# ProProject_TDeck_18650_Charger_2024-02-1.net
KiCad netlist of a schematic drawn in EasyEDA Pro
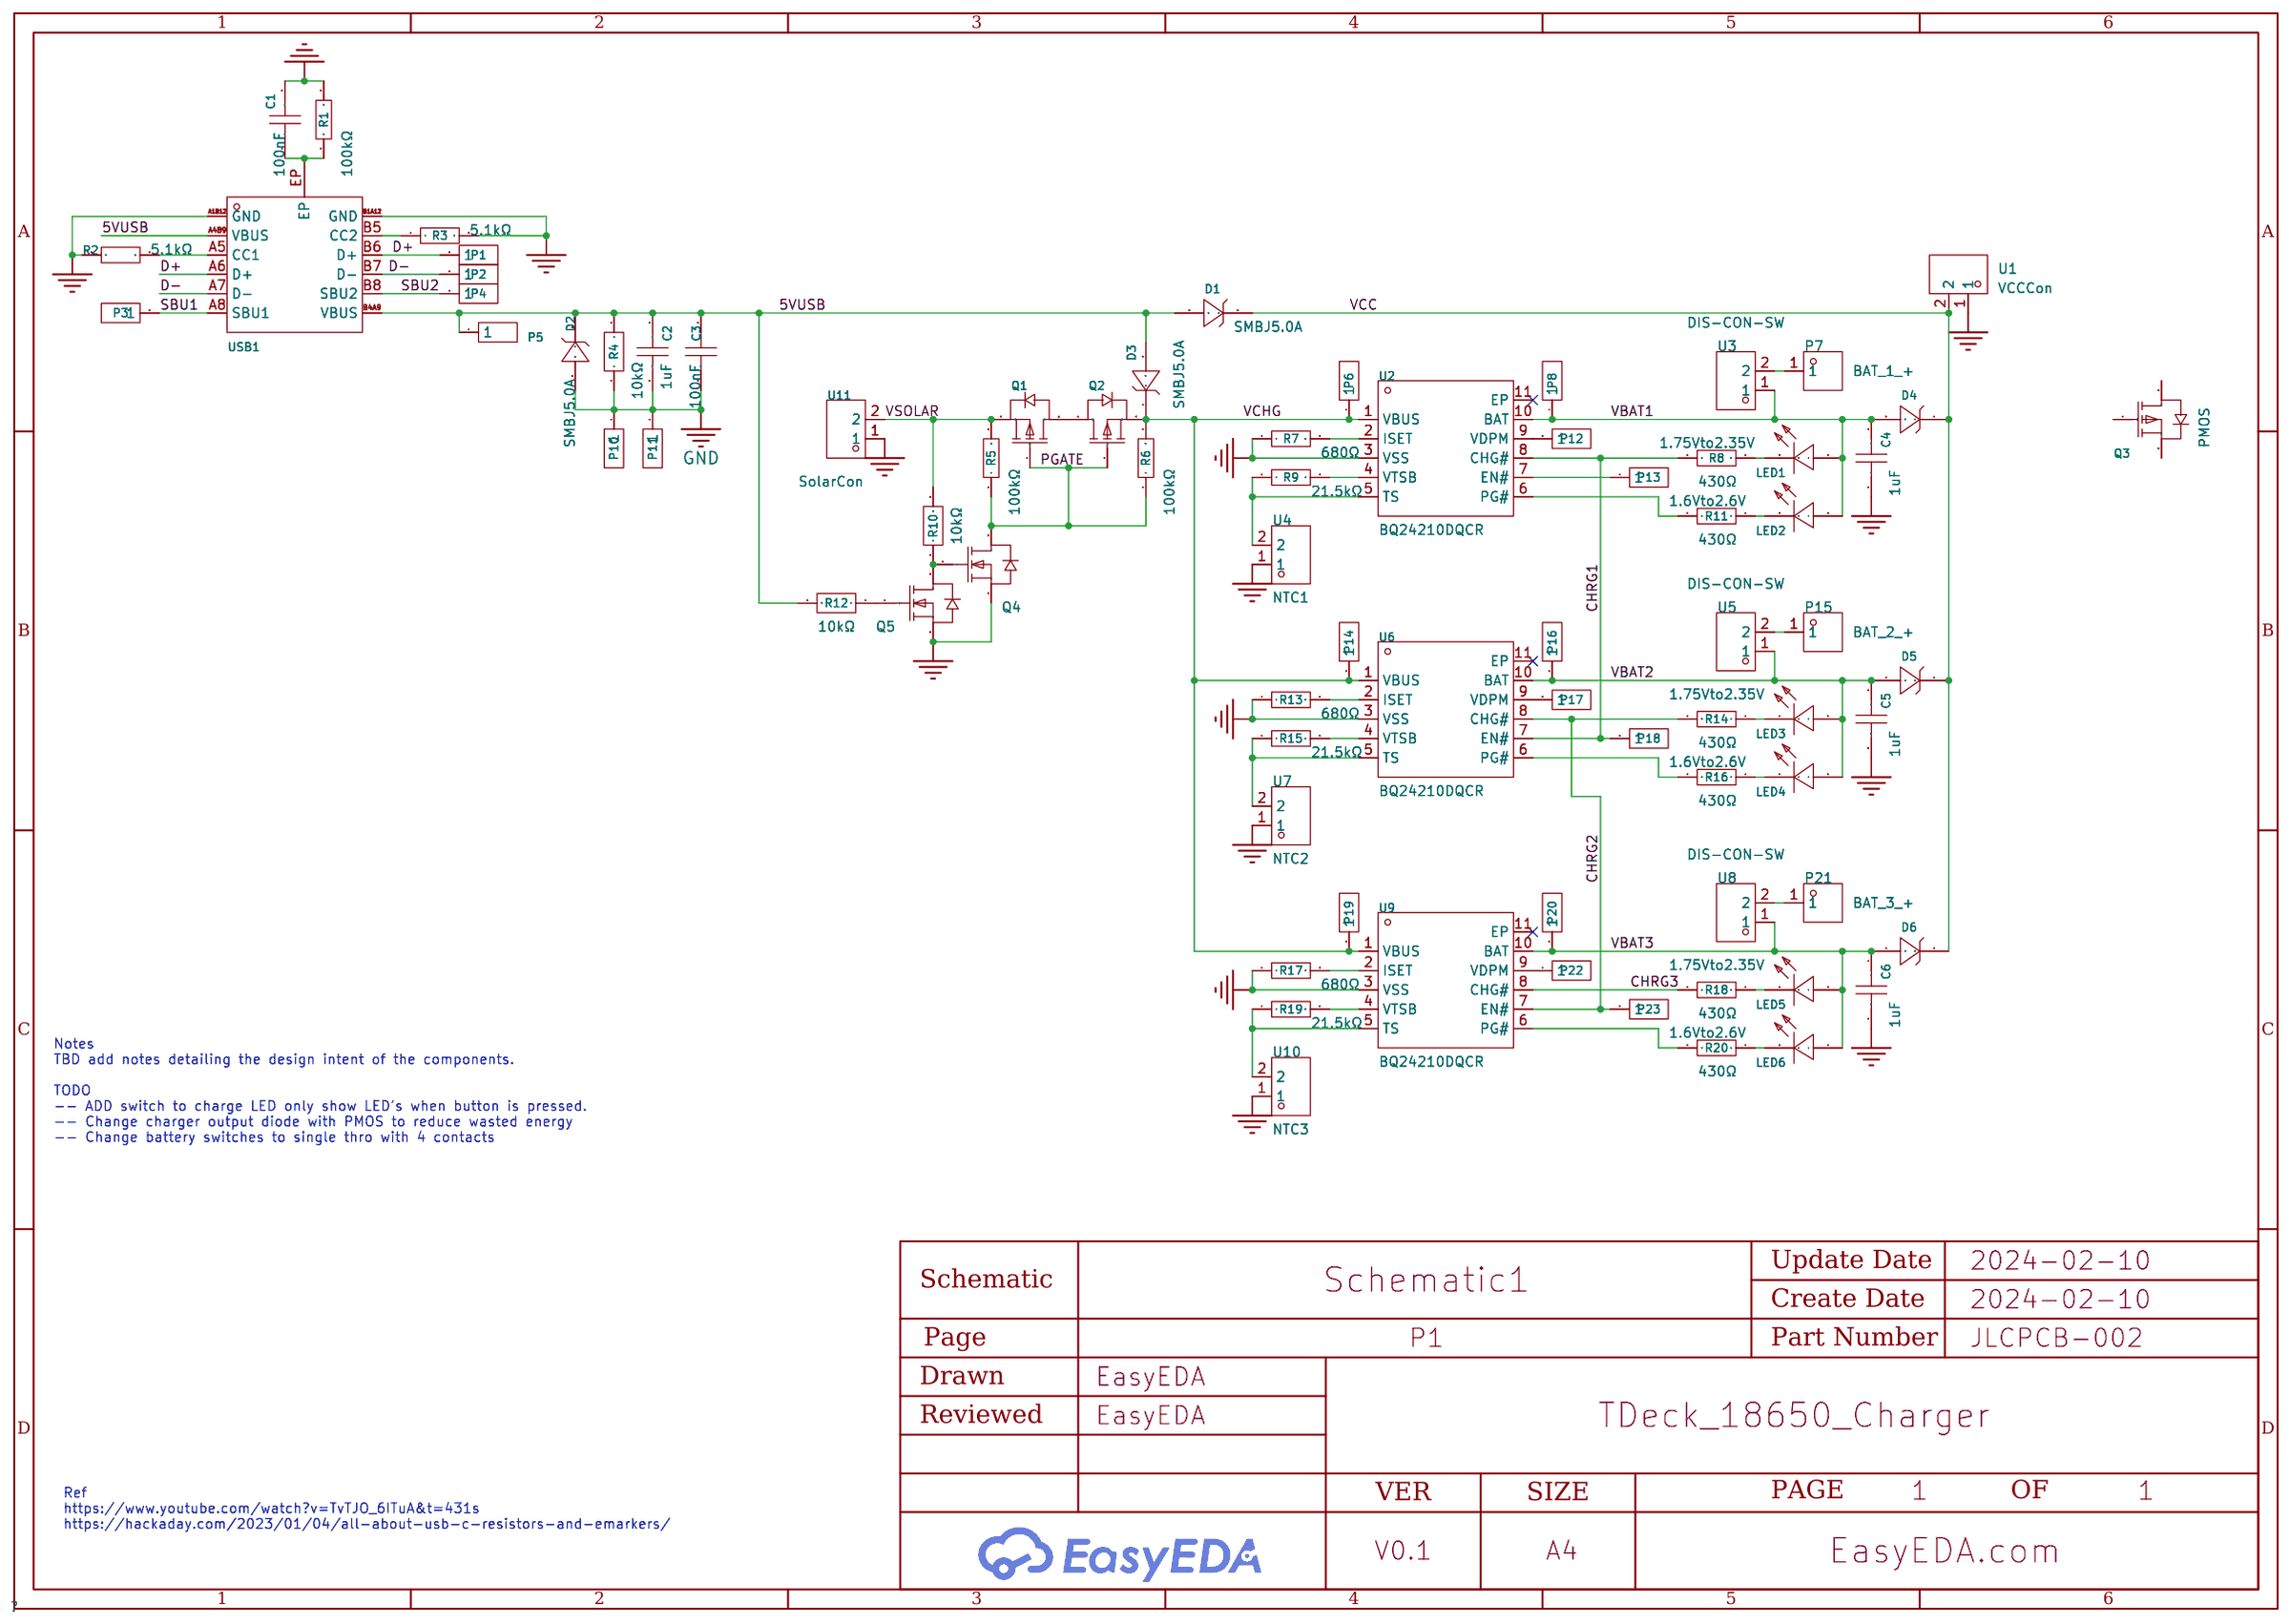
[diagram p0: schematic sheet]

(export (version "E")
  (design (tool "Eeschema 10.0.6"))
  (components
    (comp (ref "C1")
      (value "100nF")
      (footprint "easyedapro:C0603")
      (fields
        (field (name "Manufacturer Part") "CC0603KRX7R9BB104")
        (field (name "Manufacturer") "YAGEO(国巨)")
      )
      (libsource (lib "easyedapro") (part "CC0603KRX7R9BB104"))
    )
    (comp (ref "C2")
      (value "1uF")
      (footprint "easyedapro:C1206")
      (fields
        (field (name "Manufacturer Part") "CL31B105KCHNNNE")
        (field (name "Manufacturer") "SAMSUNG(三星)")
      )
      (libsource (lib "easyedapro") (part "CL31B105KCHNNNE"))
    )
    (comp (ref "C3")
      (value "100nF")
      (footprint "easyedapro:C0603")
      (fields
        (field (name "Manufacturer Part") "CC0603KRX7R9BB104")
        (field (name "Manufacturer") "YAGEO(国巨)")
      )
      (libsource (lib "easyedapro") (part "CC0603KRX7R9BB104"))
    )
    (comp (ref "C4")
      (value "1uF")
      (footprint "easyedapro:C1206")
      (fields
        (field (name "Manufacturer Part") "CL31B105KCHNNNE")
        (field (name "Manufacturer") "SAMSUNG(三星)")
      )
      (libsource (lib "easyedapro") (part "CL31B105KCHNNNE"))
    )
    (comp (ref "C5")
      (value "1uF")
      (footprint "easyedapro:C1206")
      (fields
        (field (name "Manufacturer Part") "CL31B105KCHNNNE")
        (field (name "Manufacturer") "SAMSUNG(三星)")
      )
      (libsource (lib "easyedapro") (part "CL31B105KCHNNNE"))
    )
    (comp (ref "C6")
      (value "1uF")
      (footprint "easyedapro:C1206")
      (fields
        (field (name "Manufacturer Part") "CL31B105KCHNNNE")
        (field (name "Manufacturer") "SAMSUNG(三星)")
      )
      (libsource (lib "easyedapro") (part "CL31B105KCHNNNE"))
    )
    (comp (ref "D1")
      (value "SMBJ5.0A")
      (footprint "easyedapro:SMB_L4.4-W3.6-LS5.2-RD")
      (fields (field (name "Manufacturer") "PAKER(派克微)"))
      (libsource (lib "easyedapro") (part "SMBJ5.0A_C3012487"))
    )
    (comp (ref "D2")
      (value "SMBJ5.0A")
      (footprint "easyedapro:SMB_L4.4-W3.6-LS5.2-RD")
      (fields (field (name "Manufacturer") "PAKER(派克微)"))
      (libsource (lib "easyedapro") (part "SMBJ5.0A_C3012487"))
    )
    (comp (ref "D3")
      (value "SMBJ5.0A")
      (footprint "easyedapro:SMB_L4.4-W3.6-LS5.2-RD")
      (fields (field (name "Manufacturer") "PAKER(派克微)"))
      (libsource (lib "easyedapro") (part "SMBJ5.0A_C3012487"))
    )
    (comp (ref "D4")
      (value "SMBJ5.0A")
      (footprint "easyedapro:SMB_L4.4-W3.6-LS5.2-RD")
      (fields (field (name "Manufacturer") "PAKER(派克微)"))
      (libsource (lib "easyedapro") (part "SMBJ5.0A_C3012487"))
    )
    (comp (ref "D5")
      (value "SMBJ5.0A")
      (footprint "easyedapro:SMB_L4.4-W3.6-LS5.2-RD")
      (fields (field (name "Manufacturer") "PAKER(派克微)"))
      (libsource (lib "easyedapro") (part "SMBJ5.0A_C3012487"))
    )
    (comp (ref "D6")
      (value "SMBJ5.0A")
      (footprint "easyedapro:SMB_L4.4-W3.6-LS5.2-RD")
      (fields (field (name "Manufacturer") "PAKER(派克微)"))
      (libsource (lib "easyedapro") (part "SMBJ5.0A_C3012487"))
    )
    (comp (ref "LED1")
      (value "1.75Vto2.35V")
      (footprint "easyedapro:LED0805-RD")
      (description "Emitted Color:Red")
      (fields
        (field (name "Manufacturer Part") "17-21/R6C-AQ2R2B/3T")
        (field (name "Manufacturer") "EVERLIGHT(亿光)")
      )
      (libsource (lib "easyedapro") (part "17-21/R6C-AQ2R2B/3T"))
    )
    (comp (ref "LED2")
      (value "1.6Vto2.6V")
      (footprint "easyedapro:LED0603-RD")
      (fields (field (name "Manufacturer Part") "NCD0603O2") (field (name "Manufacturer") "国星光电"))
      (libsource (lib "easyedapro") (part "FC-1608YOXK-600H08"))
    )
    (comp (ref "LED3")
      (value "1.75Vto2.35V")
      (footprint "easyedapro:LED0805-RD")
      (description "Emitted Color:Red")
      (fields
        (field (name "Manufacturer Part") "17-21/R6C-AQ2R2B/3T")
        (field (name "Manufacturer") "EVERLIGHT(亿光)")
      )
      (libsource (lib "easyedapro") (part "17-21/R6C-AQ2R2B/3T"))
    )
    (comp (ref "LED4")
      (value "1.6Vto2.6V")
      (footprint "easyedapro:LED0603-RD")
      (fields (field (name "Manufacturer Part") "NCD0603O2") (field (name "Manufacturer") "国星光电"))
      (libsource (lib "easyedapro") (part "FC-1608YOXK-600H08"))
    )
    (comp (ref "LED5")
      (value "1.75Vto2.35V")
      (footprint "easyedapro:LED0805-RD")
      (description "Emitted Color:Red")
      (fields
        (field (name "Manufacturer Part") "17-21/R6C-AQ2R2B/3T")
        (field (name "Manufacturer") "EVERLIGHT(亿光)")
      )
      (libsource (lib "easyedapro") (part "17-21/R6C-AQ2R2B/3T"))
    )
    (comp (ref "LED6")
      (value "1.6Vto2.6V")
      (footprint "easyedapro:LED0603-RD")
      (fields (field (name "Manufacturer Part") "NCD0603O2") (field (name "Manufacturer") "国星光电"))
      (libsource (lib "easyedapro") (part "FC-1608YOXK-600H08"))
    )
    (comp (ref "P1")
      (value "2.54-1*1P针")
      (footprint "easyedapro:HDR-TH_1P-P2.54-V-M")
      (fields (field (name "Manufacturer") "BOOMELE(博穆精密)"))
      (libsource (lib "easyedapro") (part "Header-Male-2.54_1x1"))
    )
    (comp (ref "P2")
      (value "2.54-1*1P针")
      (footprint "easyedapro:HDR-TH_1P-P2.54-V-M")
      (fields (field (name "Manufacturer") "BOOMELE(博穆精密)"))
      (libsource (lib "easyedapro") (part "Header-Male-2.54_1x1"))
    )
    (comp (ref "P3")
      (value "2.54-1*1P针")
      (footprint "easyedapro:HDR-TH_1P-P2.54-V-M")
      (fields (field (name "Manufacturer") "BOOMELE(博穆精密)"))
      (libsource (lib "easyedapro") (part "Header-Male-2.54_1x1"))
    )
    (comp (ref "P4")
      (value "2.54-1*1P针")
      (footprint "easyedapro:HDR-TH_1P-P2.54-V-M")
      (fields (field (name "Manufacturer") "BOOMELE(博穆精密)"))
      (libsource (lib "easyedapro") (part "Header-Male-2.54_1x1"))
    )
    (comp (ref "P5")
      (value "2.54-1*1P针")
      (footprint "easyedapro:HDR-TH_1P-P2.54-V-M")
      (fields (field (name "Manufacturer") "BOOMELE(博穆精密)"))
      (libsource (lib "easyedapro") (part "Header-Male-2.54_1x1"))
    )
    (comp (ref "P6")
      (value "2.54-1*1P针")
      (footprint "easyedapro:HDR-TH_1P-P2.54-V-M")
      (fields (field (name "Manufacturer") "BOOMELE(博穆精密)"))
      (libsource (lib "easyedapro") (part "Header-Male-2.54_1x1"))
    )
    (comp (ref "P7")
      (value "BAT_1_+")
      (footprint "easyedapro:SMD_BD4.0-L4.0-W4.0-D1.0")
      (fields (field (name "Manufacturer Part") "PAD"))
      (libsource (lib "easyedapro") (part "PAD"))
    )
    (comp (ref "P8")
      (value "2.54-1*1P针")
      (footprint "easyedapro:HDR-TH_1P-P2.54-V-M")
      (fields (field (name "Manufacturer") "BOOMELE(博穆精密)"))
      (libsource (lib "easyedapro") (part "Header-Male-2.54_1x1"))
    )
    (comp (ref "P10")
      (value "2.54-1*1P针")
      (footprint "easyedapro:HDR-TH_1P-P2.54-V-M")
      (fields (field (name "Manufacturer") "BOOMELE(博穆精密)"))
      (libsource (lib "easyedapro") (part "Header-Male-2.54_1x1"))
    )
    (comp (ref "P11")
      (value "2.54-1*1P针")
      (footprint "easyedapro:HDR-TH_1P-P2.54-V-M")
      (fields (field (name "Manufacturer") "BOOMELE(博穆精密)"))
      (libsource (lib "easyedapro") (part "Header-Male-2.54_1x1"))
    )
    (comp (ref "P12")
      (value "2.54-1*1P针")
      (footprint "easyedapro:HDR-TH_1P-P2.54-V-M")
      (fields (field (name "Manufacturer") "BOOMELE(博穆精密)"))
      (libsource (lib "easyedapro") (part "Header-Male-2.54_1x1"))
    )
    (comp (ref "P13")
      (value "2.54-1*1P针")
      (footprint "easyedapro:HDR-TH_1P-P2.54-V-M")
      (fields (field (name "Manufacturer") "BOOMELE(博穆精密)"))
      (libsource (lib "easyedapro") (part "Header-Male-2.54_1x1"))
    )
    (comp (ref "P14")
      (value "2.54-1*1P针")
      (footprint "easyedapro:HDR-TH_1P-P2.54-V-M")
      (fields (field (name "Manufacturer") "BOOMELE(博穆精密)"))
      (libsource (lib "easyedapro") (part "Header-Male-2.54_1x1"))
    )
    (comp (ref "P15")
      (value "BAT_2_+")
      (footprint "easyedapro:SMD_BD4.0-L4.0-W4.0-D1.0")
      (fields (field (name "Manufacturer Part") "PAD"))
      (libsource (lib "easyedapro") (part "PAD"))
    )
    (comp (ref "P16")
      (value "2.54-1*1P针")
      (footprint "easyedapro:HDR-TH_1P-P2.54-V-M")
      (fields (field (name "Manufacturer") "BOOMELE(博穆精密)"))
      (libsource (lib "easyedapro") (part "Header-Male-2.54_1x1"))
    )
    (comp (ref "P17")
      (value "2.54-1*1P针")
      (footprint "easyedapro:HDR-TH_1P-P2.54-V-M")
      (fields (field (name "Manufacturer") "BOOMELE(博穆精密)"))
      (libsource (lib "easyedapro") (part "Header-Male-2.54_1x1"))
    )
    (comp (ref "P18")
      (value "2.54-1*1P针")
      (footprint "easyedapro:HDR-TH_1P-P2.54-V-M")
      (fields (field (name "Manufacturer") "BOOMELE(博穆精密)"))
      (libsource (lib "easyedapro") (part "Header-Male-2.54_1x1"))
    )
    (comp (ref "P19")
      (value "2.54-1*1P针")
      (footprint "easyedapro:HDR-TH_1P-P2.54-V-M")
      (fields (field (name "Manufacturer") "BOOMELE(博穆精密)"))
      (libsource (lib "easyedapro") (part "Header-Male-2.54_1x1"))
    )
    (comp (ref "P20")
      (value "2.54-1*1P针")
      (footprint "easyedapro:HDR-TH_1P-P2.54-V-M")
      (fields (field (name "Manufacturer") "BOOMELE(博穆精密)"))
      (libsource (lib "easyedapro") (part "Header-Male-2.54_1x1"))
    )
    (comp (ref "P21")
      (value "BAT_3_+")
      (footprint "easyedapro:SMD_BD4.0-L4.0-W4.0-D1.0")
      (fields (field (name "Manufacturer Part") "PAD"))
      (libsource (lib "easyedapro") (part "PAD"))
    )
    (comp (ref "P22")
      (value "2.54-1*1P针")
      (footprint "easyedapro:HDR-TH_1P-P2.54-V-M")
      (fields (field (name "Manufacturer") "BOOMELE(博穆精密)"))
      (libsource (lib "easyedapro") (part "Header-Male-2.54_1x1"))
    )
    (comp (ref "P23")
      (value "2.54-1*1P针")
      (footprint "easyedapro:HDR-TH_1P-P2.54-V-M")
      (fields (field (name "Manufacturer") "BOOMELE(博穆精密)"))
      (libsource (lib "easyedapro") (part "Header-Male-2.54_1x1"))
    )
    (comp (ref "Q1")
      (value "SI2301")
      (footprint "easyedapro:SOT-23-3_L2.9-W1.3-P1.90-LS2.4-BR")
      (fields (field (name "Manufacturer") "YONGYUTAI(永裕泰)"))
      (libsource (lib "easyedapro") (part "SI2301_C2891731"))
    )
    (comp (ref "Q2")
      (value "SI2301")
      (footprint "easyedapro:SOT-23-3_L2.9-W1.3-P1.90-LS2.4-BR")
      (fields (field (name "Manufacturer") "YONGYUTAI(永裕泰)"))
      (libsource (lib "easyedapro") (part "SI2301_C2891731"))
    )
    (comp (ref "Q3")
      (value "PMOS")
      (footprint "easyedapro:SOT-23-3_L2.9-W1.3-P1.90-LS2.4-BR")
      (fields (field (name "Manufacturer Part") "SI2301") (field (name "Manufacturer") "YONGYUTAI(永裕泰)"))
      (libsource (lib "easyedapro") (part "SI2301_C2891731"))
    )
    (comp (ref "Q4")
      (value "AO3400A")
      (footprint "easyedapro:SOT-23-3_L2.9-W1.6-P1.90-LS2.8-BR")
      (fields (field (name "Manufacturer") "AOS"))
      (libsource (lib "easyedapro") (part "AO3400A"))
    )
    (comp (ref "Q5")
      (value "AO3400A")
      (footprint "easyedapro:SOT-23-3_L2.9-W1.6-P1.90-LS2.8-BR")
      (fields (field (name "Manufacturer") "AOS"))
      (libsource (lib "easyedapro") (part "AO3400A"))
    )
    (comp (ref "R1")
      (value "100kΩ")
      (footprint "easyedapro:R0805")
      (fields
        (field (name "Manufacturer Part") "0805W8F1003T5E")
        (field (name "Manufacturer") "UNI-ROYAL(厚声)")
      )
      (libsource (lib "easyedapro") (part "0805W8F1003T5E_C149504"))
    )
    (comp (ref "R2")
      (value "5.1kΩ")
      (footprint "easyedapro:R0805")
      (fields
        (field (name "Manufacturer Part") "0805W8F5101T5E")
        (field (name "Manufacturer") "UNI-ROYAL(厚声)")
      )
      (libsource (lib "easyedapro") (part "0805W8F5101T5E"))
    )
    (comp (ref "R3")
      (value "5.1kΩ")
      (footprint "easyedapro:R0805")
      (fields
        (field (name "Manufacturer Part") "0805W8F5101T5E")
        (field (name "Manufacturer") "UNI-ROYAL(厚声)")
      )
      (libsource (lib "easyedapro") (part "0805W8F5101T5E"))
    )
    (comp (ref "R4")
      (value "10kΩ")
      (footprint "easyedapro:R0805")
      (fields (field (name "Manufacturer Part") "AR05DTD1002") (field (name "Manufacturer") "Viking(光颉)"))
      (libsource (lib "easyedapro") (part "AR05DTD1002"))
    )
    (comp (ref "R5")
      (value "100kΩ")
      (footprint "easyedapro:R0805")
      (fields
        (field (name "Manufacturer Part") "0805W8F1003T5E")
        (field (name "Manufacturer") "UNI-ROYAL(厚声)")
      )
      (libsource (lib "easyedapro") (part "0805W8F1003T5E_C149504"))
    )
    (comp (ref "R6")
      (value "100kΩ")
      (footprint "easyedapro:R0805")
      (fields
        (field (name "Manufacturer Part") "0805W8F1003T5E")
        (field (name "Manufacturer") "UNI-ROYAL(厚声)")
      )
      (libsource (lib "easyedapro") (part "0805W8F1003T5E_C149504"))
    )
    (comp (ref "R7")
      (value "680Ω")
      (footprint "easyedapro:R0805")
      (fields
        (field (name "Manufacturer Part") "0805W8F6800T5E")
        (field (name "Manufacturer") "UNI-ROYAL(厚声)")
      )
      (libsource (lib "easyedapro") (part "0805W8F6800T5E"))
    )
    (comp (ref "R8")
      (value "430Ω")
      (footprint "easyedapro:R0603")
      (fields
        (field (name "Manufacturer Part") "0603WAF4300T5E")
        (field (name "Manufacturer") "UNI-ROYAL(厚声)")
      )
      (libsource (lib "easyedapro") (part "0603WAF4300T5E"))
    )
    (comp (ref "R9")
      (value "21.5kΩ")
      (footprint "easyedapro:R0805")
      (fields (field (name "Manufacturer Part") "CR0805-FX-2152ELF") (field (name "Manufacturer") "BOURNS"))
      (libsource (lib "easyedapro") (part "CR0805-FX-2152ELF"))
    )
    (comp (ref "R10")
      (value "10kΩ")
      (footprint "easyedapro:R0805")
      (fields (field (name "Manufacturer Part") "AR05DTD1002") (field (name "Manufacturer") "Viking(光颉)"))
      (libsource (lib "easyedapro") (part "AR05DTD1002"))
    )
    (comp (ref "R11")
      (value "430Ω")
      (footprint "easyedapro:R0603")
      (fields
        (field (name "Manufacturer Part") "0603WAF4300T5E")
        (field (name "Manufacturer") "UNI-ROYAL(厚声)")
      )
      (libsource (lib "easyedapro") (part "0603WAF4300T5E"))
    )
    (comp (ref "R12")
      (value "10kΩ")
      (footprint "easyedapro:R0805")
      (fields (field (name "Manufacturer Part") "AR05DTD1002") (field (name "Manufacturer") "Viking(光颉)"))
      (libsource (lib "easyedapro") (part "AR05DTD1002"))
    )
    (comp (ref "R13")
      (value "680Ω")
      (footprint "easyedapro:R0805")
      (fields
        (field (name "Manufacturer Part") "0805W8F6800T5E")
        (field (name "Manufacturer") "UNI-ROYAL(厚声)")
      )
      (libsource (lib "easyedapro") (part "0805W8F6800T5E"))
    )
    (comp (ref "R14")
      (value "430Ω")
      (footprint "easyedapro:R0603")
      (fields
        (field (name "Manufacturer Part") "0603WAF4300T5E")
        (field (name "Manufacturer") "UNI-ROYAL(厚声)")
      )
      (libsource (lib "easyedapro") (part "0603WAF4300T5E"))
    )
    (comp (ref "R15")
      (value "21.5kΩ")
      (footprint "easyedapro:R0805")
      (fields (field (name "Manufacturer Part") "CR0805-FX-2152ELF") (field (name "Manufacturer") "BOURNS"))
      (libsource (lib "easyedapro") (part "CR0805-FX-2152ELF"))
    )
    (comp (ref "R16")
      (value "430Ω")
      (footprint "easyedapro:R0603")
      (fields
        (field (name "Manufacturer Part") "0603WAF4300T5E")
        (field (name "Manufacturer") "UNI-ROYAL(厚声)")
      )
      (libsource (lib "easyedapro") (part "0603WAF4300T5E"))
    )
    (comp (ref "R17")
      (value "680Ω")
      (footprint "easyedapro:R0805")
      (fields
        (field (name "Manufacturer Part") "0805W8F6800T5E")
        (field (name "Manufacturer") "UNI-ROYAL(厚声)")
      )
      (libsource (lib "easyedapro") (part "0805W8F6800T5E"))
    )
    (comp (ref "R18")
      (value "430Ω")
      (footprint "easyedapro:R0603")
      (fields
        (field (name "Manufacturer Part") "0603WAF4300T5E")
        (field (name "Manufacturer") "UNI-ROYAL(厚声)")
      )
      (libsource (lib "easyedapro") (part "0603WAF4300T5E"))
    )
    (comp (ref "R19")
      (value "21.5kΩ")
      (footprint "easyedapro:R0805")
      (fields (field (name "Manufacturer Part") "CR0805-FX-2152ELF") (field (name "Manufacturer") "BOURNS"))
      (libsource (lib "easyedapro") (part "CR0805-FX-2152ELF"))
    )
    (comp (ref "R20")
      (value "430Ω")
      (footprint "easyedapro:R0603")
      (fields
        (field (name "Manufacturer Part") "0603WAF4300T5E")
        (field (name "Manufacturer") "UNI-ROYAL(厚声)")
      )
      (libsource (lib "easyedapro") (part "0603WAF4300T5E"))
    )
    (comp (ref "U1")
      (value "VCCCon")
      (footprint "easyedapro:HDR-TH_2P-P2.54-V-M-2")
      (fields
        (field (name "Manufacturer Part") "5-146472-2")
        (field (name "Manufacturer") "TE Connectivity(泰科电子)")
      )
      (libsource (lib "easyedapro") (part "5-146472-2"))
    )
    (comp (ref "U2")
      (value "BQ24210DQCR")
      (footprint "easyedapro:WSON-10_L3.0-W2.0-P0.50-BL-EP")
      (fields (field (name "Manufacturer") "TI(德州仪器)"))
      (libsource (lib "easyedapro") (part "BQ24210DQCR"))
    )
    (comp (ref "U3")
      (value "DIS-CON-SW")
      (footprint "easyedapro:HDR-TH_2P-P2.54-V-M-2")
      (fields
        (field (name "Manufacturer Part") "5-146472-2")
        (field (name "Manufacturer") "TE Connectivity(泰科电子)")
      )
      (libsource (lib "easyedapro") (part "5-146472-2"))
    )
    (comp (ref "U4")
      (value "NTC1")
      (footprint "easyedapro:HDR-TH_2P-P2.54-V-M-2")
      (fields
        (field (name "Manufacturer Part") "5-146472-2")
        (field (name "Manufacturer") "TE Connectivity(泰科电子)")
      )
      (libsource (lib "easyedapro") (part "5-146472-2"))
    )
    (comp (ref "U5")
      (value "DIS-CON-SW")
      (footprint "easyedapro:HDR-TH_2P-P2.54-V-M-2")
      (fields
        (field (name "Manufacturer Part") "5-146472-2")
        (field (name "Manufacturer") "TE Connectivity(泰科电子)")
      )
      (libsource (lib "easyedapro") (part "5-146472-2"))
    )
    (comp (ref "U6")
      (value "BQ24210DQCR")
      (footprint "easyedapro:WSON-10_L3.0-W2.0-P0.50-BL-EP")
      (fields (field (name "Manufacturer") "TI(德州仪器)"))
      (libsource (lib "easyedapro") (part "BQ24210DQCR"))
    )
    (comp (ref "U7")
      (value "NTC2")
      (footprint "easyedapro:HDR-TH_2P-P2.54-V-M-2")
      (fields
        (field (name "Manufacturer Part") "5-146472-2")
        (field (name "Manufacturer") "TE Connectivity(泰科电子)")
      )
      (libsource (lib "easyedapro") (part "5-146472-2"))
    )
    (comp (ref "U8")
      (value "DIS-CON-SW")
      (footprint "easyedapro:HDR-TH_2P-P2.54-V-M-2")
      (fields
        (field (name "Manufacturer Part") "5-146472-2")
        (field (name "Manufacturer") "TE Connectivity(泰科电子)")
      )
      (libsource (lib "easyedapro") (part "5-146472-2"))
    )
    (comp (ref "U9")
      (value "BQ24210DQCR")
      (footprint "easyedapro:WSON-10_L3.0-W2.0-P0.50-BL-EP")
      (fields (field (name "Manufacturer") "TI(德州仪器)"))
      (libsource (lib "easyedapro") (part "BQ24210DQCR"))
    )
    (comp (ref "U10")
      (value "NTC3")
      (footprint "easyedapro:HDR-TH_2P-P2.54-V-M-2")
      (fields
        (field (name "Manufacturer Part") "5-146472-2")
        (field (name "Manufacturer") "TE Connectivity(泰科电子)")
      )
      (libsource (lib "easyedapro") (part "5-146472-2"))
    )
    (comp (ref "U11")
      (value "SolarCon")
      (footprint "easyedapro:CONN-TH_XY308-2.54-2P")
      (fields
        (field (name "Manufacturer Part") "XY308-2.54-2P")
        (field (name "Manufacturer") "XINLAIYA(新莱亚)")
      )
      (libsource (lib "easyedapro") (part "XY308-2.54-2P"))
    )
    (comp (ref "USB1")
      (value "TYPEC-304-ACP16")
      (footprint "easyedapro:USB-C-SMD_TYPE-C-16P-1")
      (fields (field (name "Manufacturer") "XUNPU(讯普)"))
      (libsource (lib "easyedapro") (part "TYPEC-304-ACP16"))
    )
  )
  (nets
    (net (code "1") (name "/5VUSB") (class "Default")
      (node (ref "C2") (pin "1") (pinfunction "1_1") (pintype "input"))
      (node (ref "C3") (pin "2") (pinfunction "2_2") (pintype "input"))
      (node (ref "D1") (pin "2") (pinfunction "2_2") (pintype "input"))
      (node (ref "D2") (pin "1") (pinfunction "1_1") (pintype "input"))
      (node (ref "D3") (pin "2") (pinfunction "2_2") (pintype "input"))
      (node (ref "P5") (pin "1") (pinfunction "1_1") (pintype "input"))
      (node (ref "R12") (pin "2") (pinfunction "2_2") (pintype "input"))
      (node (ref "R4") (pin "2") (pinfunction "2_2") (pintype "input"))
      (node (ref "USB1") (pin "A4B9") (pinfunction "VBUS_A4B9") (pintype "input"))
      (node (ref "USB1") (pin "B4A9") (pinfunction "VBUS_B4A9") (pintype "input"))
    )
    (net (code "2") (name "/CHRG1") (class "Default")
      (node (ref "P18") (pin "1") (pinfunction "1_1") (pintype "input"))
      (node (ref "R8") (pin "2") (pinfunction "2_2") (pintype "input"))
      (node (ref "U2") (pin "8") (pinfunction "CHG#_8") (pintype "input"))
      (node (ref "U6") (pin "7") (pinfunction "EN#_7") (pintype "input"))
    )
    (net (code "3") (name "/CHRG2") (class "Default")
      (node (ref "P23") (pin "1") (pinfunction "1_1") (pintype "input"))
      (node (ref "R14") (pin "2") (pinfunction "2_2") (pintype "input"))
      (node (ref "U6") (pin "8") (pinfunction "CHG#_8") (pintype "input"))
      (node (ref "U9") (pin "7") (pinfunction "EN#_7") (pintype "input"))
    )
    (net (code "4") (name "/CHRG3") (class "Default")
      (node (ref "R18") (pin "2") (pinfunction "2_2") (pintype "input"))
      (node (ref "U9") (pin "8") (pinfunction "CHG#_8") (pintype "input"))
    )
    (net (code "5") (name "/D+") (class "Default")
      (node (ref "P1") (pin "1") (pinfunction "1_1") (pintype "input"))
      (node (ref "USB1") (pin "A6") (pinfunction "D+_A6") (pintype "input"))
      (node (ref "USB1") (pin "B6") (pinfunction "D+_B6") (pintype "input"))
    )
    (net (code "6") (name "/D-") (class "Default")
      (node (ref "P2") (pin "1") (pinfunction "1_1") (pintype "input"))
      (node (ref "USB1") (pin "A7") (pinfunction "D-_A7") (pintype "input"))
      (node (ref "USB1") (pin "B7") (pinfunction "D-_B7") (pintype "input"))
    )
    (net (code "7") (name "/PGATE") (class "Default")
      (node (ref "Q1") (pin "1") (pinfunction "G_1") (pintype "input"))
      (node (ref "Q2") (pin "1") (pinfunction "G_1") (pintype "input"))
      (node (ref "Q4") (pin "3") (pinfunction "D_3") (pintype "input"))
      (node (ref "R5") (pin "1") (pinfunction "1_1") (pintype "input"))
      (node (ref "R6") (pin "1") (pinfunction "1_1") (pintype "input"))
    )
    (net (code "8") (name "/SBU1") (class "Default")
      (node (ref "P3") (pin "1") (pinfunction "1_1") (pintype "input"))
      (node (ref "USB1") (pin "A8") (pinfunction "SBU1_A8") (pintype "input"))
    )
    (net (code "9") (name "/SBU2") (class "Default")
      (node (ref "P4") (pin "1") (pinfunction "1_1") (pintype "input"))
      (node (ref "USB1") (pin "B8") (pinfunction "SBU2_B8") (pintype "input"))
    )
    (net (code "10") (name "/VBAT1") (class "Default")
      (node (ref "C4") (pin "1") (pinfunction "1_1") (pintype "input"))
      (node (ref "D4") (pin "2") (pinfunction "2_2") (pintype "input"))
      (node (ref "LED1") (pin "2") (pinfunction "A_2") (pintype "input"))
      (node (ref "LED2") (pin "2") (pinfunction "A_2") (pintype "input"))
      (node (ref "P8") (pin "1") (pinfunction "1_1") (pintype "input"))
      (node (ref "U2") (pin "10") (pinfunction "BAT_10") (pintype "input"))
      (node (ref "U3") (pin "1") (pinfunction "1_1") (pintype "unspecified"))
    )
    (net (code "11") (name "/VBAT2") (class "Default")
      (node (ref "C5") (pin "1") (pinfunction "1_1") (pintype "input"))
      (node (ref "D5") (pin "2") (pinfunction "2_2") (pintype "input"))
      (node (ref "LED3") (pin "2") (pinfunction "A_2") (pintype "input"))
      (node (ref "LED4") (pin "2") (pinfunction "A_2") (pintype "input"))
      (node (ref "P16") (pin "1") (pinfunction "1_1") (pintype "input"))
      (node (ref "U5") (pin "1") (pinfunction "1_1") (pintype "unspecified"))
      (node (ref "U6") (pin "10") (pinfunction "BAT_10") (pintype "input"))
    )
    (net (code "12") (name "/VBAT3") (class "Default")
      (node (ref "C6") (pin "1") (pinfunction "1_1") (pintype "input"))
      (node (ref "D6") (pin "2") (pinfunction "2_2") (pintype "input"))
      (node (ref "LED5") (pin "2") (pinfunction "A_2") (pintype "input"))
      (node (ref "LED6") (pin "2") (pinfunction "A_2") (pintype "input"))
      (node (ref "P20") (pin "1") (pinfunction "1_1") (pintype "input"))
      (node (ref "U8") (pin "1") (pinfunction "1_1") (pintype "unspecified"))
      (node (ref "U9") (pin "10") (pinfunction "BAT_10") (pintype "input"))
    )
    (net (code "13") (name "/VCC") (class "Default")
      (node (ref "D1") (pin "1") (pinfunction "1_1") (pintype "input"))
      (node (ref "D4") (pin "1") (pinfunction "1_1") (pintype "input"))
      (node (ref "D5") (pin "1") (pinfunction "1_1") (pintype "input"))
      (node (ref "D6") (pin "1") (pinfunction "1_1") (pintype "input"))
      (node (ref "U1") (pin "2") (pinfunction "2_2") (pintype "unspecified"))
    )
    (net (code "14") (name "/VCHG") (class "Default")
      (node (ref "D3") (pin "1") (pinfunction "1_1") (pintype "input"))
      (node (ref "P14") (pin "1") (pinfunction "1_1") (pintype "input"))
      (node (ref "P19") (pin "1") (pinfunction "1_1") (pintype "input"))
      (node (ref "P6") (pin "1") (pinfunction "1_1") (pintype "input"))
      (node (ref "Q2") (pin "2") (pinfunction "S_2") (pintype "input"))
      (node (ref "R6") (pin "2") (pinfunction "2_2") (pintype "input"))
      (node (ref "U2") (pin "1") (pinfunction "VBUS_1") (pintype "input"))
      (node (ref "U6") (pin "1") (pinfunction "VBUS_1") (pintype "input"))
      (node (ref "U9") (pin "1") (pinfunction "VBUS_1") (pintype "input"))
    )
    (net (code "15") (name "/VSOLAR") (class "Default")
      (node (ref "Q1") (pin "2") (pinfunction "S_2") (pintype "input"))
      (node (ref "R10") (pin "2") (pinfunction "2_2") (pintype "input"))
      (node (ref "R5") (pin "2") (pinfunction "2_2") (pintype "input"))
      (node (ref "U11") (pin "2") (pinfunction "2_2") (pintype "input"))
    )
    (net (code "16") (name "GND") (class "Default")
      (node (ref "C1") (pin "2") (pinfunction "2_2") (pintype "input"))
      (node (ref "C2") (pin "2") (pinfunction "2_2") (pintype "input"))
      (node (ref "C3") (pin "1") (pinfunction "1_1") (pintype "input"))
      (node (ref "C4") (pin "2") (pinfunction "2_2") (pintype "input"))
      (node (ref "C5") (pin "2") (pinfunction "2_2") (pintype "input"))
      (node (ref "C6") (pin "2") (pinfunction "2_2") (pintype "input"))
      (node (ref "D2") (pin "2") (pinfunction "2_2") (pintype "input"))
      (node (ref "P10") (pin "1") (pinfunction "1_1") (pintype "input"))
      (node (ref "P11") (pin "1") (pinfunction "1_1") (pintype "input"))
      (node (ref "Q4") (pin "2") (pinfunction "S_2") (pintype "input"))
      (node (ref "Q5") (pin "2") (pinfunction "S_2") (pintype "input"))
      (node (ref "R1") (pin "2") (pinfunction "2_2") (pintype "input"))
      (node (ref "R13") (pin "1") (pinfunction "1_1") (pintype "input"))
      (node (ref "R17") (pin "1") (pinfunction "1_1") (pintype "input"))
      (node (ref "R2") (pin "1") (pinfunction "1_1") (pintype "input"))
      (node (ref "R3") (pin "2") (pinfunction "2_2") (pintype "input"))
      (node (ref "R4") (pin "1") (pinfunction "1_1") (pintype "input"))
      (node (ref "R7") (pin "1") (pinfunction "1_1") (pintype "input"))
      (node (ref "U1") (pin "1") (pinfunction "1_1") (pintype "unspecified"))
      (node (ref "U10") (pin "1") (pinfunction "1_1") (pintype "unspecified"))
      (node (ref "U11") (pin "1") (pinfunction "1_1") (pintype "input"))
      (node (ref "U2") (pin "3") (pinfunction "VSS_3") (pintype "input"))
      (node (ref "U4") (pin "1") (pinfunction "1_1") (pintype "unspecified"))
      (node (ref "U6") (pin "3") (pinfunction "VSS_3") (pintype "input"))
      (node (ref "U7") (pin "1") (pinfunction "1_1") (pintype "unspecified"))
      (node (ref "U9") (pin "3") (pinfunction "VSS_3") (pintype "input"))
      (node (ref "USB1") (pin "A1B12") (pinfunction "GND_A1B12") (pintype "input"))
      (node (ref "USB1") (pin "B1A12") (pinfunction "GND_B1A12") (pintype "input"))
    )
    (net (code "17") (name "Net-(C1-Pad1)") (class "Default")
      (node (ref "C1") (pin "1") (pinfunction "1_1") (pintype "input"))
      (node (ref "R1") (pin "1") (pinfunction "1_1") (pintype "input"))
      (node (ref "USB1") (pin "EP") (pinfunction "EP_EP") (pintype "input"))
    )
    (net (code "18") (name "Net-(LED1-K)") (class "Default")
      (node (ref "LED1") (pin "1") (pinfunction "K_1") (pintype "input"))
      (node (ref "R8") (pin "1") (pinfunction "1_1") (pintype "input"))
    )
    (net (code "19") (name "Net-(LED2-K)") (class "Default")
      (node (ref "LED2") (pin "1") (pinfunction "K_1") (pintype "input"))
      (node (ref "R11") (pin "1") (pinfunction "1_1") (pintype "input"))
    )
    (net (code "20") (name "Net-(LED3-K)") (class "Default")
      (node (ref "LED3") (pin "1") (pinfunction "K_1") (pintype "input"))
      (node (ref "R14") (pin "1") (pinfunction "1_1") (pintype "input"))
    )
    (net (code "21") (name "Net-(LED4-K)") (class "Default")
      (node (ref "LED4") (pin "1") (pinfunction "K_1") (pintype "input"))
      (node (ref "R16") (pin "1") (pinfunction "1_1") (pintype "input"))
    )
    (net (code "22") (name "Net-(LED5-K)") (class "Default")
      (node (ref "LED5") (pin "1") (pinfunction "K_1") (pintype "input"))
      (node (ref "R18") (pin "1") (pinfunction "1_1") (pintype "input"))
    )
    (net (code "23") (name "Net-(LED6-K)") (class "Default")
      (node (ref "LED6") (pin "1") (pinfunction "K_1") (pintype "input"))
      (node (ref "R20") (pin "1") (pinfunction "1_1") (pintype "input"))
    )
    (net (code "24") (name "Net-(P7-Pad1)") (class "Default")
      (node (ref "P7") (pin "1") (pinfunction "1_1") (pintype "input"))
      (node (ref "U3") (pin "2") (pinfunction "2_2") (pintype "unspecified"))
    )
    (net (code "25") (name "Net-(P15-Pad1)") (class "Default")
      (node (ref "P15") (pin "1") (pinfunction "1_1") (pintype "input"))
      (node (ref "U5") (pin "2") (pinfunction "2_2") (pintype "unspecified"))
    )
    (net (code "26") (name "Net-(P21-Pad1)") (class "Default")
      (node (ref "P21") (pin "1") (pinfunction "1_1") (pintype "input"))
      (node (ref "U8") (pin "2") (pinfunction "2_2") (pintype "unspecified"))
    )
    (net (code "27") (name "Net-(Q1-D)") (class "Default")
      (node (ref "Q1") (pin "3") (pinfunction "D_3") (pintype "input"))
      (node (ref "Q2") (pin "3") (pinfunction "D_3") (pintype "input"))
    )
    (net (code "28") (name "Net-(Q4-G)") (class "Default")
      (node (ref "Q4") (pin "1") (pinfunction "G_1") (pintype "input"))
      (node (ref "Q5") (pin "3") (pinfunction "D_3") (pintype "input"))
      (node (ref "R10") (pin "1") (pinfunction "1_1") (pintype "input"))
    )
    (net (code "29") (name "Net-(Q5-G)") (class "Default")
      (node (ref "Q5") (pin "1") (pinfunction "G_1") (pintype "input"))
      (node (ref "R12") (pin "1") (pinfunction "1_1") (pintype "input"))
    )
    (net (code "30") (name "Net-(U2-EN#)") (class "Default")
      (node (ref "P13") (pin "1") (pinfunction "1_1") (pintype "input"))
      (node (ref "U2") (pin "7") (pinfunction "EN#_7") (pintype "input"))
    )
    (net (code "31") (name "Net-(U2-ISET)") (class "Default")
      (node (ref "R7") (pin "2") (pinfunction "2_2") (pintype "input"))
      (node (ref "U2") (pin "2") (pinfunction "ISET_2") (pintype "input"))
    )
    (net (code "32") (name "Net-(U2-PG#)") (class "Default")
      (node (ref "R11") (pin "2") (pinfunction "2_2") (pintype "input"))
      (node (ref "U2") (pin "6") (pinfunction "PG#_6") (pintype "input"))
    )
    (net (code "33") (name "Net-(U2-TS)") (class "Default")
      (node (ref "R9") (pin "1") (pinfunction "1_1") (pintype "input"))
      (node (ref "U2") (pin "5") (pinfunction "TS_5") (pintype "input"))
      (node (ref "U4") (pin "2") (pinfunction "2_2") (pintype "unspecified"))
    )
    (net (code "34") (name "Net-(U2-VDPM)") (class "Default")
      (node (ref "P12") (pin "1") (pinfunction "1_1") (pintype "input"))
      (node (ref "U2") (pin "9") (pinfunction "VDPM_9") (pintype "input"))
    )
    (net (code "35") (name "Net-(U2-VTSB)") (class "Default")
      (node (ref "R9") (pin "2") (pinfunction "2_2") (pintype "input"))
      (node (ref "U2") (pin "4") (pinfunction "VTSB_4") (pintype "input"))
    )
    (net (code "36") (name "Net-(U6-ISET)") (class "Default")
      (node (ref "R13") (pin "2") (pinfunction "2_2") (pintype "input"))
      (node (ref "U6") (pin "2") (pinfunction "ISET_2") (pintype "input"))
    )
    (net (code "37") (name "Net-(U6-PG#)") (class "Default")
      (node (ref "R16") (pin "2") (pinfunction "2_2") (pintype "input"))
      (node (ref "U6") (pin "6") (pinfunction "PG#_6") (pintype "input"))
    )
    (net (code "38") (name "Net-(U6-TS)") (class "Default")
      (node (ref "R15") (pin "1") (pinfunction "1_1") (pintype "input"))
      (node (ref "U6") (pin "5") (pinfunction "TS_5") (pintype "input"))
      (node (ref "U7") (pin "2") (pinfunction "2_2") (pintype "unspecified"))
    )
    (net (code "39") (name "Net-(U6-VDPM)") (class "Default")
      (node (ref "P17") (pin "1") (pinfunction "1_1") (pintype "input"))
      (node (ref "U6") (pin "9") (pinfunction "VDPM_9") (pintype "input"))
    )
    (net (code "40") (name "Net-(U6-VTSB)") (class "Default")
      (node (ref "R15") (pin "2") (pinfunction "2_2") (pintype "input"))
      (node (ref "U6") (pin "4") (pinfunction "VTSB_4") (pintype "input"))
    )
    (net (code "41") (name "Net-(U9-ISET)") (class "Default")
      (node (ref "R17") (pin "2") (pinfunction "2_2") (pintype "input"))
      (node (ref "U9") (pin "2") (pinfunction "ISET_2") (pintype "input"))
    )
    (net (code "42") (name "Net-(U9-PG#)") (class "Default")
      (node (ref "R20") (pin "2") (pinfunction "2_2") (pintype "input"))
      (node (ref "U9") (pin "6") (pinfunction "PG#_6") (pintype "input"))
    )
    (net (code "43") (name "Net-(U9-TS)") (class "Default")
      (node (ref "R19") (pin "1") (pinfunction "1_1") (pintype "input"))
      (node (ref "U10") (pin "2") (pinfunction "2_2") (pintype "unspecified"))
      (node (ref "U9") (pin "5") (pinfunction "TS_5") (pintype "input"))
    )
    (net (code "44") (name "Net-(U9-VDPM)") (class "Default")
      (node (ref "P22") (pin "1") (pinfunction "1_1") (pintype "input"))
      (node (ref "U9") (pin "9") (pinfunction "VDPM_9") (pintype "input"))
    )
    (net (code "45") (name "Net-(U9-VTSB)") (class "Default")
      (node (ref "R19") (pin "2") (pinfunction "2_2") (pintype "input"))
      (node (ref "U9") (pin "4") (pinfunction "VTSB_4") (pintype "input"))
    )
    (net (code "46") (name "Net-(USB1-CC1)") (class "Default")
      (node (ref "R2") (pin "2") (pinfunction "2_2") (pintype "input"))
      (node (ref "USB1") (pin "A5") (pinfunction "CC1_A5") (pintype "input"))
    )
    (net (code "47") (name "Net-(USB1-CC2)") (class "Default")
      (node (ref "R3") (pin "1") (pinfunction "1_1") (pintype "input"))
      (node (ref "USB1") (pin "B5") (pinfunction "CC2_B5") (pintype "input"))
    )
    (net (code "48") (name "unconnected-(Q3-D-Pad3)") (class "Default")
      (node (ref "Q3") (pin "3") (pinfunction "D_3") (pintype "input"))
    )
    (net (code "49") (name "unconnected-(Q3-G-Pad1)") (class "Default")
      (node (ref "Q3") (pin "1") (pinfunction "G_1") (pintype "input"))
    )
    (net (code "50") (name "unconnected-(Q3-S-Pad2)") (class "Default")
      (node (ref "Q3") (pin "2") (pinfunction "S_2") (pintype "input"))
    )
    (net (code "51") (name "unconnected-(U2-EP-Pad11)") (class "Default")
      (node (ref "U2") (pin "11") (pinfunction "EP_11") (pintype "input+no_connect"))
    )
    (net (code "52") (name "unconnected-(U6-EP-Pad11)") (class "Default")
      (node (ref "U6") (pin "11") (pinfunction "EP_11") (pintype "input+no_connect"))
    )
    (net (code "53") (name "unconnected-(U9-EP-Pad11)") (class "Default")
      (node (ref "U9") (pin "11") (pinfunction "EP_11") (pintype "input+no_connect"))
    )
  )
)
